# jack_driver_1.net
KiCad netlist of a schematic drawn in Altium Designer
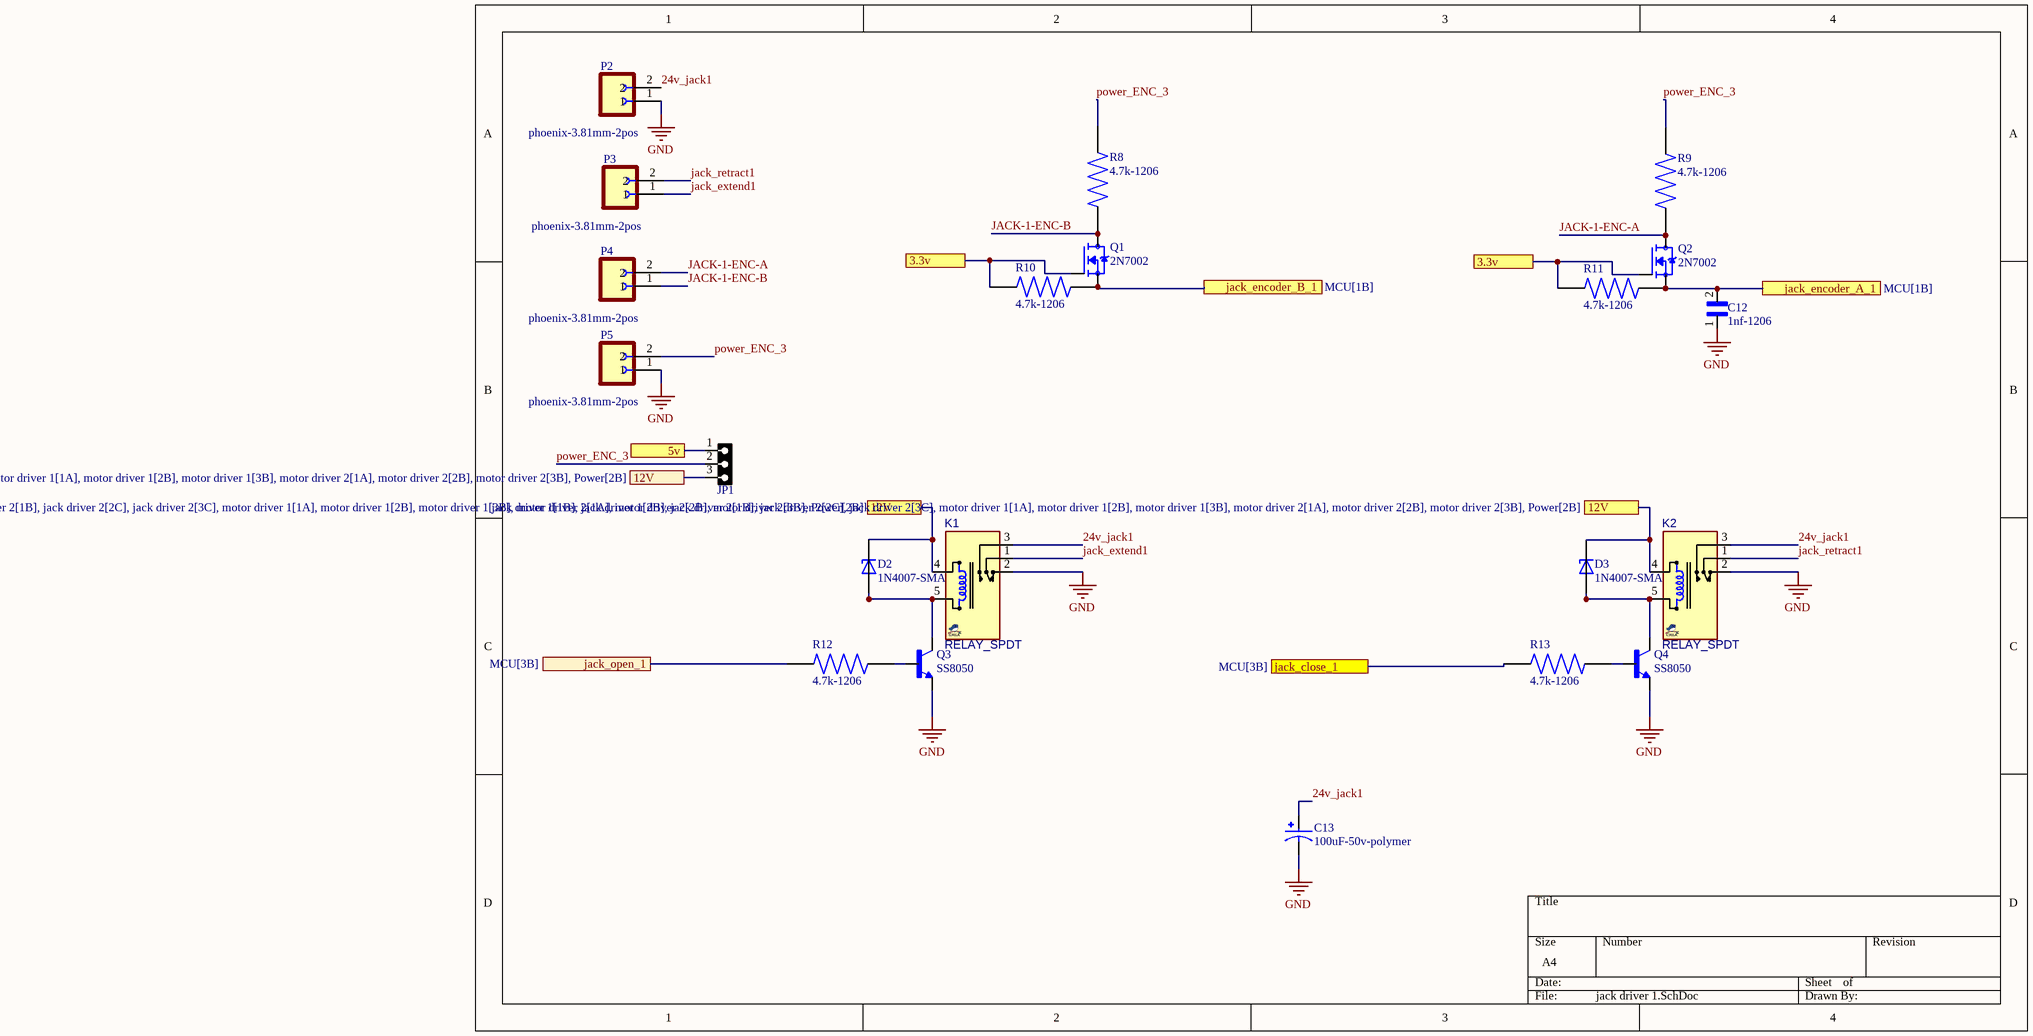
[diagram p0: jack driver 1.SchDoc]

(export (version "E")
  (design (tool "Eeschema 10.0.6"))
  (components
    (comp (ref "C12")
      (value "1nf-1206")
      (footprint "CAPC3216X180N")
      (description "1ÂµF Â±20% 50V Ceramic Capacitor X8R 1206 (3216 Metric)")
      (fields (field (name "MF") "TDK") (field (name "MP") "CGA5L3X8R1H105M160AB"))
      (libsource (lib "cap-1206") (part "CGA5L3X8R1H105M160AB"))
    )
    (comp (ref "C13")
      (value "100uF-50v-polymer")
      (footprint "CAP_EEEFN1H101L")
      (description "CAP ALUM 100UF 20% 50V SMD")
      (fields (field (name "MF") "Panasonic") (field (name "MP") "EEEFN1H101L"))
      (libsource (lib "100uF_50v") (part "EEEFN1H101L"))
    )
    (comp (ref "D2")
      (value "1N4007-SMA")
      (footprint "DIOM4325X250N")
      (description "400W, 30.4V, 5%, Unidirectional, TVS")
      (fields (field (name "MF") "Taiwan Semiconductor") (field (name "MP") "SMAJ26A"))
      (libsource (lib "diode-sma") (part "SMAJ26A"))
    )
    (comp (ref "D3")
      (value "1N4007-SMA")
      (footprint "DIOM4325X250N")
      (description "400W, 30.4V, 5%, Unidirectional, TVS")
      (fields (field (name "MF") "Taiwan Semiconductor") (field (name "MP") "SMAJ26A"))
      (libsource (lib "diode-sma") (part "SMAJ26A"))
    )
    (comp (ref "JP1")
      (value "HDRF3")
      (footprint "HDRLP_F_1X3")
      (description "CONN, HEADER, Male, pitch: 2.54mm, 3POS")
      (libsource (lib "conn_2.54mm_lp") (part "HDRLP_F_1X3"))
    )
    (comp (ref "K1")
      (value "RELAY_SPDT")
      (footprint "REL_SPDT_5_1512")
      (description "Relay, SPDT, 5P, 15.4X12.1mm, 16V/30A")
      (fields (field (name "MANF") "OMRON") (field (name "MANF_P#") "G8QN-1C4 DC12"))
      (libsource (lib "relay") (part "RELAY_SPDT_5_1512_G8QN"))
    )
    (comp (ref "K2")
      (value "RELAY_SPDT")
      (footprint "REL_SPDT_5_1512")
      (description "Relay, SPDT, 5P, 15.4X12.1mm, 16V/30A")
      (fields (field (name "MANF") "OMRON") (field (name "MANF_P#") "G8QN-1C4 DC12"))
      (libsource (lib "relay") (part "RELAY_SPDT_5_1512_G8QN"))
    )
    (comp (ref "P2")
      (value "phoenix-3.81mm-2pos")
      (footprint "PHOENIX_1803578")
      (description "2 Position Terminal Block Plug, Female Sockets 0.150 (3.81mm) 180Â° Free Hanging (In-Line)")
      (fields (field (name "MF") "Phoenix Contact") (field (name "MP") "1803578"))
      (libsource (lib "terminal-phoenix-3.81mm-2pos") (part "1803578"))
    )
    (comp (ref "P3")
      (value "phoenix-3.81mm-2pos")
      (footprint "PHOENIX_1803578")
      (description "2 Position Terminal Block Plug, Female Sockets 0.150 (3.81mm) 180Â° Free Hanging (In-Line)")
      (fields (field (name "MF") "Phoenix Contact") (field (name "MP") "1803578"))
      (libsource (lib "terminal-phoenix-3.81mm-2pos") (part "1803578"))
    )
    (comp (ref "P4")
      (value "phoenix-3.81mm-2pos")
      (footprint "PHOENIX_1803578")
      (description "2 Position Terminal Block Plug, Female Sockets 0.150 (3.81mm) 180Â° Free Hanging (In-Line)")
      (fields (field (name "MF") "Phoenix Contact") (field (name "MP") "1803578"))
      (libsource (lib "terminal-phoenix-3.81mm-2pos") (part "1803578"))
    )
    (comp (ref "P5")
      (value "phoenix-3.81mm-2pos")
      (footprint "PHOENIX_1803578")
      (description "2 Position Terminal Block Plug, Female Sockets 0.150 (3.81mm) 180Â° Free Hanging (In-Line)")
      (fields (field (name "MF") "Phoenix Contact") (field (name "MP") "1803578"))
      (libsource (lib "terminal-phoenix-3.81mm-2pos") (part "1803578"))
    )
    (comp (ref "Q1")
      (value "2N7002")
      (footprint "SOT95P240X111-3N")
      (description "N-Channel 60V 280mA (Ta) 350mW (Ta) Surface Mount SOT-23-3 (TO-236)")
      (fields (field (name "MF") "{'manufacturer': u'onsemi'}"))
      (libsource (lib "2N7002-SOT23") (part "2N7002"))
    )
    (comp (ref "Q2")
      (value "2N7002")
      (footprint "SOT95P240X111-3N")
      (description "N-Channel 60V 280mA (Ta) 350mW (Ta) Surface Mount SOT-23-3 (TO-236)")
      (fields (field (name "MF") "{'manufacturer': u'onsemi'}"))
      (libsource (lib "2N7002-SOT23") (part "2N7002"))
    )
    (comp (ref "Q3")
      (value "SS8050")
      (footprint "TRANS_SS8050-G")
      (description "Bipolar (BJT) Transistor NPN 25 V 1.5 A 100MHz 300 mW Surface Mount SOT-23-3")
      (fields (field (name "DIGI-KEY_PART_NUMBER") "641-1790-2-ND") (field (name "MP") "SS8050G"))
      (libsource (lib "SS8050-G") (part "SS8050-G"))
    )
    (comp (ref "Q4")
      (value "SS8050")
      (footprint "TRANS_SS8050-G")
      (description "Bipolar (BJT) Transistor NPN 25 V 1.5 A 100MHz 300 mW Surface Mount SOT-23-3")
      (fields (field (name "DIGI-KEY_PART_NUMBER") "641-1790-2-ND") (field (name "MP") "SS8050G"))
      (libsource (lib "SS8050-G") (part "SS8050-G"))
    )
    (comp (ref "R8")
      (value "4.7k-1206")
      (footprint "RESC3015X65N")
      (description "Res Thin Film 1206 10K Ohm 0.1% 1/8W Â±25ppm/Â°C Molded SMD SMD Paper T/R")
      (fields (field (name "MF") "TE Connectivity") (field (name "MP") "CPF1206B10KE1"))
      (libsource (lib "resistor-1206") (part "CPF1206B10KE1"))
    )
    (comp (ref "R9")
      (value "4.7k-1206")
      (footprint "RESC3015X65N")
      (description "Res Thin Film 1206 10K Ohm 0.1% 1/8W Â±25ppm/Â°C Molded SMD SMD Paper T/R")
      (fields (field (name "MF") "TE Connectivity") (field (name "MP") "CPF1206B10KE1"))
      (libsource (lib "resistor-1206") (part "CPF1206B10KE1"))
    )
    (comp (ref "R10")
      (value "4.7k-1206")
      (footprint "RESC3015X65N")
      (description "Res Thin Film 1206 10K Ohm 0.1% 1/8W Â±25ppm/Â°C Molded SMD SMD Paper T/R")
      (fields (field (name "MF") "TE Connectivity") (field (name "MP") "CPF1206B10KE1"))
      (libsource (lib "resistor-1206") (part "CPF1206B10KE1"))
    )
    (comp (ref "R11")
      (value "4.7k-1206")
      (footprint "RESC3015X65N")
      (description "Res Thin Film 1206 10K Ohm 0.1% 1/8W Â±25ppm/Â°C Molded SMD SMD Paper T/R")
      (fields (field (name "MF") "TE Connectivity") (field (name "MP") "CPF1206B10KE1"))
      (libsource (lib "resistor-1206") (part "CPF1206B10KE1"))
    )
    (comp (ref "R12")
      (value "4.7k-1206")
      (footprint "RESC3015X65N")
      (description "Res Thin Film 1206 10K Ohm 0.1% 1/8W Â±25ppm/Â°C Molded SMD SMD Paper T/R")
      (fields (field (name "MF") "TE Connectivity") (field (name "MP") "CPF1206B10KE1"))
      (libsource (lib "resistor-1206") (part "CPF1206B10KE1"))
    )
    (comp (ref "R13")
      (value "4.7k-1206")
      (footprint "RESC3015X65N")
      (description "Res Thin Film 1206 10K Ohm 0.1% 1/8W Â±25ppm/Â°C Molded SMD SMD Paper T/R")
      (fields (field (name "MF") "TE Connectivity") (field (name "MP") "CPF1206B10KE1"))
      (libsource (lib "resistor-1206") (part "CPF1206B10KE1"))
    )
  )
  (nets
    (net (code "1") (name "/3.3v") (class "Default")
      (node (ref "Q1") (pin "1") (pinfunction "G_1") (pintype "passive"))
      (node (ref "Q2") (pin "1") (pinfunction "G_1") (pintype "passive"))
      (node (ref "R10") (pin "2") (pinfunction "2_2") (pintype "passive"))
      (node (ref "R11") (pin "2") (pinfunction "2_2") (pintype "passive"))
    )
    (net (code "2") (name "/5v") (class "Default")
      (node (ref "JP1") (pin "1") (pinfunction "1_1") (pintype "passive"))
    )
    (net (code "3") (name "/12V") (class "Default")
      (node (ref "D2") (pin "C") (pinfunction "C_C") (pintype "passive"))
      (node (ref "D3") (pin "C") (pinfunction "C_C") (pintype "passive"))
      (node (ref "JP1") (pin "3") (pinfunction "3_3") (pintype "passive"))
      (node (ref "K1") (pin "4") (pinfunction "T1_4") (pintype "passive"))
      (node (ref "K2") (pin "4") (pinfunction "T1_4") (pintype "passive"))
    )
    (net (code "4") (name "/24v_jack1") (class "Default")
      (node (ref "C13") (pin "1") (pinfunction "1_1") (pintype "passive"))
      (node (ref "K1") (pin "3") (pinfunction "NO_3") (pintype "passive"))
      (node (ref "K2") (pin "3") (pinfunction "NO_3") (pintype "passive"))
      (node (ref "P2") (pin "2") (pinfunction "2_2") (pintype "passive"))
    )
    (net (code "5") (name "/JACK-1-ENC-A") (class "Default")
      (node (ref "P4") (pin "2") (pinfunction "2_2") (pintype "passive"))
      (node (ref "Q2") (pin "3") (pinfunction "D_3") (pintype "passive"))
      (node (ref "R9") (pin "1") (pinfunction "1_1") (pintype "passive"))
    )
    (net (code "6") (name "/JACK-1-ENC-B") (class "Default")
      (node (ref "P4") (pin "1") (pinfunction "1_1") (pintype "passive"))
      (node (ref "Q1") (pin "3") (pinfunction "D_3") (pintype "passive"))
      (node (ref "R8") (pin "1") (pinfunction "1_1") (pintype "passive"))
    )
    (net (code "7") (name "/jack_close_1") (class "Default")
      (node (ref "R13") (pin "2") (pinfunction "2_2") (pintype "passive"))
    )
    (net (code "8") (name "/jack_encoder_A_1") (class "Default")
      (node (ref "C12") (pin "2") (pinfunction "2_2") (pintype "passive"))
      (node (ref "Q2") (pin "2") (pinfunction "S_2") (pintype "passive"))
      (node (ref "R11") (pin "1") (pinfunction "1_1") (pintype "passive"))
    )
    (net (code "9") (name "/jack_encoder_B_1") (class "Default")
      (node (ref "Q1") (pin "2") (pinfunction "S_2") (pintype "passive"))
      (node (ref "R10") (pin "1") (pinfunction "1_1") (pintype "passive"))
    )
    (net (code "10") (name "/jack_extend1") (class "Default")
      (node (ref "K1") (pin "1") (pinfunction "COM_1") (pintype "passive"))
      (node (ref "P3") (pin "1") (pinfunction "1_1") (pintype "passive"))
    )
    (net (code "11") (name "/jack_open_1") (class "Default")
      (node (ref "R12") (pin "2") (pinfunction "2_2") (pintype "passive"))
    )
    (net (code "12") (name "/jack_retract1") (class "Default")
      (node (ref "K2") (pin "1") (pinfunction "COM_1") (pintype "passive"))
      (node (ref "P3") (pin "2") (pinfunction "2_2") (pintype "passive"))
    )
    (net (code "13") (name "/power_ENC_3") (class "Default")
      (node (ref "JP1") (pin "2") (pinfunction "2_2") (pintype "passive"))
      (node (ref "P5") (pin "2") (pinfunction "2_2") (pintype "passive"))
      (node (ref "R8") (pin "2") (pinfunction "2_2") (pintype "passive"))
      (node (ref "R9") (pin "2") (pinfunction "2_2") (pintype "passive"))
    )
    (net (code "14") (name "GND") (class "Default")
      (node (ref "C12") (pin "1") (pinfunction "1_1") (pintype "passive"))
      (node (ref "C13") (pin "2") (pinfunction "2_2") (pintype "passive"))
      (node (ref "K1") (pin "2") (pinfunction "NC_2") (pintype "passive"))
      (node (ref "K2") (pin "2") (pinfunction "NC_2") (pintype "passive"))
      (node (ref "P2") (pin "1") (pinfunction "1_1") (pintype "passive"))
      (node (ref "P5") (pin "1") (pinfunction "1_1") (pintype "passive"))
      (node (ref "Q3") (pin "2") (pinfunction "E_2") (pintype "passive"))
      (node (ref "Q4") (pin "2") (pinfunction "E_2") (pintype "passive"))
    )
    (net (code "15") (name "Net-(K1-T2)") (class "Default")
      (node (ref "D2") (pin "A") (pinfunction "A_A") (pintype "passive"))
      (node (ref "K1") (pin "5") (pinfunction "T2_5") (pintype "passive"))
      (node (ref "Q3") (pin "3") (pinfunction "C_3") (pintype "passive"))
    )
    (net (code "16") (name "Net-(K2-T2)") (class "Default")
      (node (ref "D3") (pin "A") (pinfunction "A_A") (pintype "passive"))
      (node (ref "K2") (pin "5") (pinfunction "T2_5") (pintype "passive"))
      (node (ref "Q4") (pin "3") (pinfunction "C_3") (pintype "passive"))
    )
    (net (code "17") (name "Net-(Q3-B)") (class "Default")
      (node (ref "Q3") (pin "1") (pinfunction "B_1") (pintype "passive"))
      (node (ref "R12") (pin "1") (pinfunction "1_1") (pintype "passive"))
    )
    (net (code "18") (name "Net-(Q4-B)") (class "Default")
      (node (ref "Q4") (pin "1") (pinfunction "B_1") (pintype "passive"))
      (node (ref "R13") (pin "1") (pinfunction "1_1") (pintype "passive"))
    )
  )
)
